# switches_schema.net
KiCad netlist of a schematic drawn in EAGLE
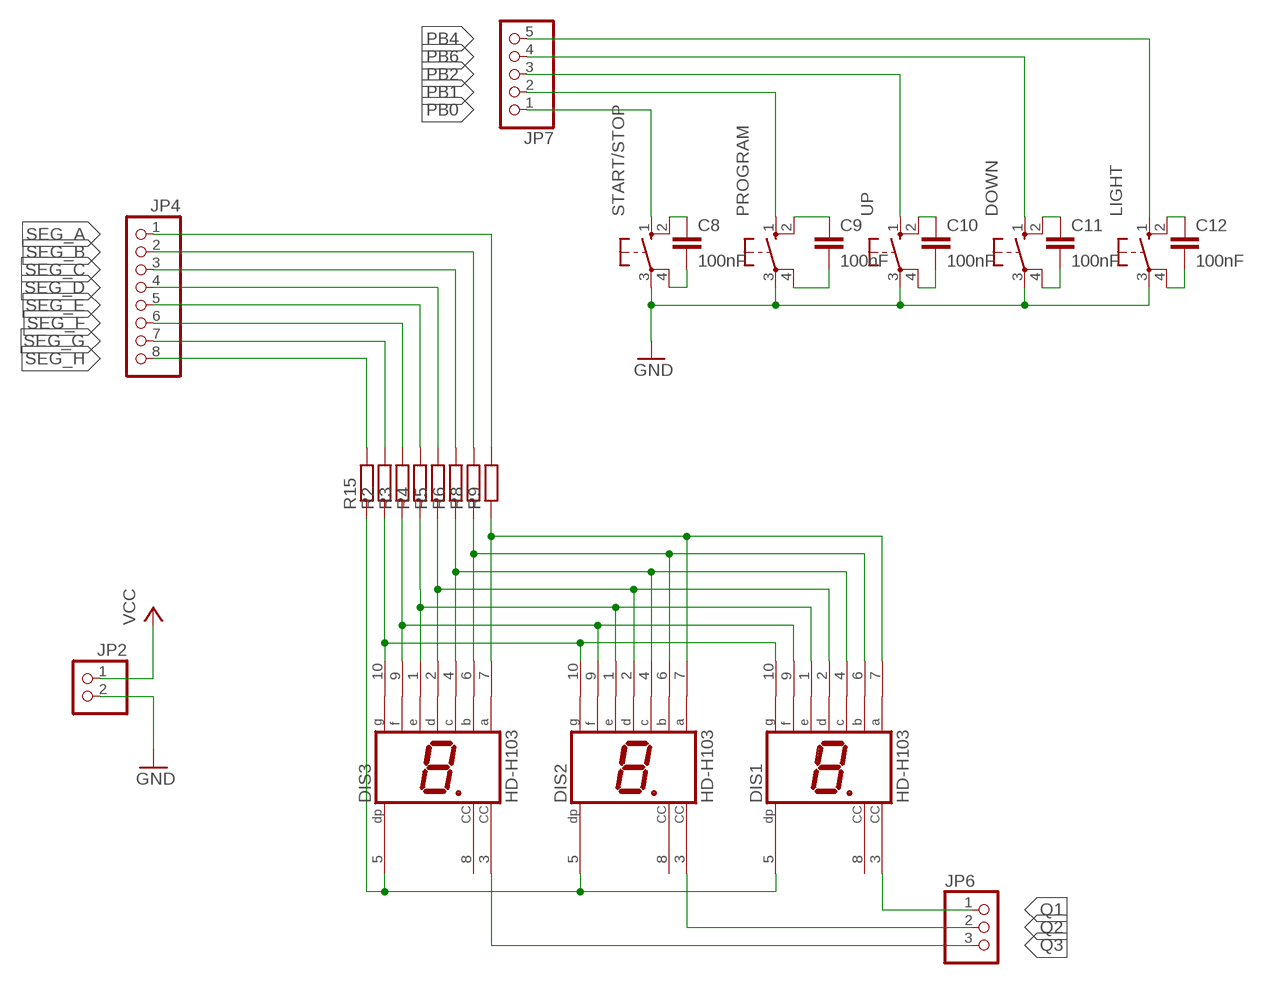
[diagram p0: schematic, sheet 1]

(export (version "E")
  (design (tool "Eeschema 10.0.6"))
  (components
    (comp (ref "C8")
      (value "100nF")
      (footprint "eagle-import:C025-024X044")
      (libsource (lib "eagle-import") (part "C-EU025-024X044"))
    )
    (comp (ref "C9")
      (value "100nF")
      (footprint "eagle-import:C025-024X044")
      (libsource (lib "eagle-import") (part "C-EU025-024X044"))
    )
    (comp (ref "C10")
      (value "100nF")
      (footprint "eagle-import:C025-024X044")
      (libsource (lib "eagle-import") (part "C-EU025-024X044"))
    )
    (comp (ref "C11")
      (value "100nF")
      (footprint "eagle-import:C025-024X044")
      (libsource (lib "eagle-import") (part "C-EU025-024X044"))
    )
    (comp (ref "C12")
      (value "100nF")
      (footprint "eagle-import:C025-024X044")
      (libsource (lib "eagle-import") (part "C-EU025-024X044"))
    )
    (comp (ref "DIS1")
      (value "HD-H103")
      (footprint "eagle-import:HDSP-M")
      (libsource (lib "eagle-import") (part "HD-H103"))
    )
    (comp (ref "DIS2")
      (value "HD-H103")
      (footprint "eagle-import:HDSP-M")
      (libsource (lib "eagle-import") (part "HD-H103"))
    )
    (comp (ref "DIS3")
      (value "HD-H103")
      (footprint "eagle-import:HDSP-M")
      (libsource (lib "eagle-import") (part "HD-H103"))
    )
    (comp (ref "DOWN")
      (value "10-XX")
      (footprint "eagle-import:B3F-10XX")
      (fields (field (name "MPN") "B3F-1000"))
      (libsource (lib "eagle-import") (part "10-XX"))
    )
    (comp (ref "JP2")
      (value "PINHD-1X2")
      (footprint "eagle-import:1X02")
      (libsource (lib "eagle-import") (part "PINHD-1X2"))
    )
    (comp (ref "JP4")
      (value "PINHD-1X8")
      (footprint "eagle-import:1X08")
      (libsource (lib "eagle-import") (part "PINHD-1X8"))
    )
    (comp (ref "JP6")
      (value "PINHD-1X3")
      (footprint "eagle-import:1X03")
      (libsource (lib "eagle-import") (part "PINHD-1X3"))
    )
    (comp (ref "JP7")
      (value "PINHD-1X5")
      (footprint "eagle-import:1X05")
      (libsource (lib "eagle-import") (part "PINHD-1X5"))
    )
    (comp (ref "LIGHT")
      (value "10-XX")
      (footprint "eagle-import:B3F-10XX")
      (fields (field (name "MPN") "B3F-1000"))
      (libsource (lib "eagle-import") (part "10-XX"))
    )
    (comp (ref "PROGRAM")
      (value "10-XX")
      (footprint "eagle-import:B3F-10XX")
      (fields (field (name "MPN") "B3F-1000"))
      (libsource (lib "eagle-import") (part "10-XX"))
    )
    (comp (ref "R2")
      (value "R-EU_0204/7")
      (footprint "eagle-import:0204_7")
      (libsource (lib "eagle-import") (part "R-EU_0204/7"))
    )
    (comp (ref "R3")
      (value "R-EU_0204/7")
      (footprint "eagle-import:0204_7")
      (libsource (lib "eagle-import") (part "R-EU_0204/7"))
    )
    (comp (ref "R4")
      (value "R-EU_0204/7")
      (footprint "eagle-import:0204_7")
      (libsource (lib "eagle-import") (part "R-EU_0204/7"))
    )
    (comp (ref "R5")
      (value "R-EU_0204/7")
      (footprint "eagle-import:0204_7")
      (libsource (lib "eagle-import") (part "R-EU_0204/7"))
    )
    (comp (ref "R6")
      (value "R-EU_0204/7")
      (footprint "eagle-import:0204_7")
      (libsource (lib "eagle-import") (part "R-EU_0204/7"))
    )
    (comp (ref "R8")
      (value "R-EU_0204/7")
      (footprint "eagle-import:0204_7")
      (libsource (lib "eagle-import") (part "R-EU_0204/7"))
    )
    (comp (ref "R9")
      (value "R-EU_0204/7")
      (footprint "eagle-import:0204_7")
      (libsource (lib "eagle-import") (part "R-EU_0204/7"))
    )
    (comp (ref "R15")
      (value "R-EU_0204/7")
      (footprint "eagle-import:0204_7")
      (libsource (lib "eagle-import") (part "R-EU_0204/7"))
    )
    (comp (ref "START/STOP")
      (value "10-XX")
      (footprint "eagle-import:B3F-10XX")
      (fields (field (name "MPN") "B3F-1000"))
      (libsource (lib "eagle-import") (part "10-XX"))
    )
    (comp (ref "UP")
      (value "10-XX")
      (footprint "eagle-import:B3F-10XX")
      (fields (field (name "MPN") "B3F-1000"))
      (libsource (lib "eagle-import") (part "10-XX"))
    )
  )
  (nets
    (net (code "1") (name "GND") (class "Default")
      (node (ref "DOWN") (pin "3") (pinfunction "P_3") (pintype "passive"))
      (node (ref "JP2") (pin "2") (pinfunction "2_2") (pintype "passive"))
      (node (ref "LIGHT") (pin "3") (pinfunction "P_3") (pintype "passive"))
      (node (ref "PROGRAM") (pin "3") (pinfunction "P_3") (pintype "passive"))
      (node (ref "START/STOP") (pin "3") (pinfunction "P_3") (pintype "passive"))
      (node (ref "UP") (pin "3") (pinfunction "P_3") (pintype "passive"))
    )
    (net (code "2") (name "Net-(DIS1-A)") (class "Default")
      (node (ref "DIS1") (pin "7") (pinfunction "A_7") (pintype "passive"))
      (node (ref "DIS2") (pin "7") (pinfunction "A_7") (pintype "passive"))
      (node (ref "DIS3") (pin "7") (pinfunction "A_7") (pintype "passive"))
      (node (ref "R9") (pin "1") (pinfunction "1_1") (pintype "passive"))
    )
    (net (code "3") (name "Net-(DIS1-B)") (class "Default")
      (node (ref "DIS1") (pin "6") (pinfunction "B_6") (pintype "passive"))
      (node (ref "DIS2") (pin "6") (pinfunction "B_6") (pintype "passive"))
      (node (ref "DIS3") (pin "6") (pinfunction "B_6") (pintype "passive"))
      (node (ref "R8") (pin "1") (pinfunction "1_1") (pintype "passive"))
    )
    (net (code "4") (name "Net-(DIS1-C)") (class "Default")
      (node (ref "DIS1") (pin "4") (pinfunction "C_4") (pintype "passive"))
      (node (ref "DIS2") (pin "4") (pinfunction "C_4") (pintype "passive"))
      (node (ref "DIS3") (pin "4") (pinfunction "C_4") (pintype "passive"))
      (node (ref "R6") (pin "1") (pinfunction "1_1") (pintype "passive"))
    )
    (net (code "5") (name "Net-(DIS1-D)") (class "Default")
      (node (ref "DIS1") (pin "2") (pinfunction "D_2") (pintype "passive"))
      (node (ref "DIS2") (pin "2") (pinfunction "D_2") (pintype "passive"))
      (node (ref "DIS3") (pin "2") (pinfunction "D_2") (pintype "passive"))
      (node (ref "R5") (pin "1") (pinfunction "1_1") (pintype "passive"))
    )
    (net (code "6") (name "Net-(DIS1-DP)") (class "Default")
      (node (ref "DIS1") (pin "5") (pinfunction "DP_5") (pintype "passive"))
      (node (ref "DIS2") (pin "5") (pinfunction "DP_5") (pintype "passive"))
      (node (ref "DIS3") (pin "5") (pinfunction "DP_5") (pintype "passive"))
      (node (ref "R15") (pin "1") (pinfunction "1_1") (pintype "passive"))
    )
    (net (code "7") (name "Net-(DIS1-E)") (class "Default")
      (node (ref "DIS1") (pin "1") (pinfunction "E_1") (pintype "passive"))
      (node (ref "DIS2") (pin "1") (pinfunction "E_1") (pintype "passive"))
      (node (ref "DIS3") (pin "1") (pinfunction "E_1") (pintype "passive"))
      (node (ref "R4") (pin "1") (pinfunction "1_1") (pintype "passive"))
    )
    (net (code "8") (name "Net-(DIS1-F)") (class "Default")
      (node (ref "DIS1") (pin "9") (pinfunction "F_9") (pintype "passive"))
      (node (ref "DIS2") (pin "9") (pinfunction "F_9") (pintype "passive"))
      (node (ref "DIS3") (pin "9") (pinfunction "F_9") (pintype "passive"))
      (node (ref "R3") (pin "1") (pinfunction "1_1") (pintype "passive"))
    )
    (net (code "9") (name "Net-(DIS1-G)") (class "Default")
      (node (ref "DIS1") (pin "10") (pinfunction "G_10") (pintype "passive"))
      (node (ref "DIS2") (pin "10") (pinfunction "G_10") (pintype "passive"))
      (node (ref "DIS3") (pin "10") (pinfunction "G_10") (pintype "passive"))
      (node (ref "R2") (pin "1") (pinfunction "1_1") (pintype "passive"))
    )
    (net (code "10") (name "Net-(DOWN-P1)") (class "Default")
      (node (ref "C11") (pin "2") (pinfunction "2_2") (pintype "passive"))
      (node (ref "DOWN") (pin "4") (pinfunction "P1_4") (pintype "passive"))
    )
    (net (code "11") (name "Net-(DOWN-S1)") (class "Default")
      (node (ref "C11") (pin "1") (pinfunction "1_1") (pintype "passive"))
      (node (ref "DOWN") (pin "2") (pinfunction "S1_2") (pintype "passive"))
    )
    (net (code "12") (name "Net-(LIGHT-P1)") (class "Default")
      (node (ref "C12") (pin "2") (pinfunction "2_2") (pintype "passive"))
      (node (ref "LIGHT") (pin "4") (pinfunction "P1_4") (pintype "passive"))
    )
    (net (code "13") (name "Net-(LIGHT-S1)") (class "Default")
      (node (ref "C12") (pin "1") (pinfunction "1_1") (pintype "passive"))
      (node (ref "LIGHT") (pin "2") (pinfunction "S1_2") (pintype "passive"))
    )
    (net (code "14") (name "Net-(PROGRAM-P1)") (class "Default")
      (node (ref "C9") (pin "2") (pinfunction "2_2") (pintype "passive"))
      (node (ref "PROGRAM") (pin "4") (pinfunction "P1_4") (pintype "passive"))
    )
    (net (code "15") (name "Net-(PROGRAM-S1)") (class "Default")
      (node (ref "C9") (pin "1") (pinfunction "1_1") (pintype "passive"))
      (node (ref "PROGRAM") (pin "2") (pinfunction "S1_2") (pintype "passive"))
    )
    (net (code "16") (name "Net-(START/STOP-P1)") (class "Default")
      (node (ref "C8") (pin "2") (pinfunction "2_2") (pintype "passive"))
      (node (ref "START/STOP") (pin "4") (pinfunction "P1_4") (pintype "passive"))
    )
    (net (code "17") (name "Net-(START/STOP-S1)") (class "Default")
      (node (ref "C8") (pin "1") (pinfunction "1_1") (pintype "passive"))
      (node (ref "START/STOP") (pin "2") (pinfunction "S1_2") (pintype "passive"))
    )
    (net (code "18") (name "Net-(UP-P1)") (class "Default")
      (node (ref "C10") (pin "2") (pinfunction "2_2") (pintype "passive"))
      (node (ref "UP") (pin "4") (pinfunction "P1_4") (pintype "passive"))
    )
    (net (code "19") (name "Net-(UP-S1)") (class "Default")
      (node (ref "C10") (pin "1") (pinfunction "1_1") (pintype "passive"))
      (node (ref "UP") (pin "2") (pinfunction "S1_2") (pintype "passive"))
    )
    (net (code "20") (name "PB0") (class "Default")
      (node (ref "JP7") (pin "1") (pinfunction "1_1") (pintype "passive"))
      (node (ref "START/STOP") (pin "1") (pinfunction "S_1") (pintype "passive"))
    )
    (net (code "21") (name "PB1") (class "Default")
      (node (ref "JP7") (pin "2") (pinfunction "2_2") (pintype "passive"))
      (node (ref "PROGRAM") (pin "1") (pinfunction "S_1") (pintype "passive"))
    )
    (net (code "22") (name "PB2") (class "Default")
      (node (ref "JP7") (pin "3") (pinfunction "3_3") (pintype "passive"))
      (node (ref "UP") (pin "1") (pinfunction "S_1") (pintype "passive"))
    )
    (net (code "23") (name "PB4") (class "Default")
      (node (ref "JP7") (pin "5") (pinfunction "5_5") (pintype "passive"))
      (node (ref "LIGHT") (pin "1") (pinfunction "S_1") (pintype "passive"))
    )
    (net (code "24") (name "PB6") (class "Default")
      (node (ref "DOWN") (pin "1") (pinfunction "S_1") (pintype "passive"))
      (node (ref "JP7") (pin "4") (pinfunction "4_4") (pintype "passive"))
    )
    (net (code "25") (name "Q1") (class "Default")
      (node (ref "DIS1") (pin "3") (pinfunction "CC_3") (pintype "passive"))
      (node (ref "JP6") (pin "1") (pinfunction "1_1") (pintype "passive"))
    )
    (net (code "26") (name "Q2") (class "Default")
      (node (ref "DIS2") (pin "3") (pinfunction "CC_3") (pintype "passive"))
      (node (ref "JP6") (pin "2") (pinfunction "2_2") (pintype "passive"))
    )
    (net (code "27") (name "Q3") (class "Default")
      (node (ref "DIS3") (pin "3") (pinfunction "CC_3") (pintype "passive"))
      (node (ref "JP6") (pin "3") (pinfunction "3_3") (pintype "passive"))
    )
    (net (code "28") (name "SEG_A") (class "Default")
      (node (ref "JP4") (pin "1") (pinfunction "1_1") (pintype "passive"))
      (node (ref "R9") (pin "2") (pinfunction "2_2") (pintype "passive"))
    )
    (net (code "29") (name "SEG_B") (class "Default")
      (node (ref "JP4") (pin "2") (pinfunction "2_2") (pintype "passive"))
      (node (ref "R8") (pin "2") (pinfunction "2_2") (pintype "passive"))
    )
    (net (code "30") (name "SEG_C") (class "Default")
      (node (ref "JP4") (pin "3") (pinfunction "3_3") (pintype "passive"))
      (node (ref "R6") (pin "2") (pinfunction "2_2") (pintype "passive"))
    )
    (net (code "31") (name "SEG_D") (class "Default")
      (node (ref "JP4") (pin "4") (pinfunction "4_4") (pintype "passive"))
      (node (ref "R5") (pin "2") (pinfunction "2_2") (pintype "passive"))
    )
    (net (code "32") (name "SEG_E") (class "Default")
      (node (ref "JP4") (pin "5") (pinfunction "5_5") (pintype "passive"))
      (node (ref "R4") (pin "2") (pinfunction "2_2") (pintype "passive"))
    )
    (net (code "33") (name "SEG_F") (class "Default")
      (node (ref "JP4") (pin "6") (pinfunction "6_6") (pintype "passive"))
      (node (ref "R3") (pin "2") (pinfunction "2_2") (pintype "passive"))
    )
    (net (code "34") (name "SEG_G") (class "Default")
      (node (ref "JP4") (pin "7") (pinfunction "7_7") (pintype "passive"))
      (node (ref "R2") (pin "2") (pinfunction "2_2") (pintype "passive"))
    )
    (net (code "35") (name "SEG_H") (class "Default")
      (node (ref "JP4") (pin "8") (pinfunction "8_8") (pintype "passive"))
      (node (ref "R15") (pin "2") (pinfunction "2_2") (pintype "passive"))
    )
    (net (code "36") (name "VCC") (class "Default")
      (node (ref "JP2") (pin "1") (pinfunction "1_1") (pintype "passive"))
    )
    (net (code "37") (name "unconnected-(DIS1-CC-Pad8)") (class "Default")
      (node (ref "DIS1") (pin "8") (pinfunction "CC_8") (pintype "passive"))
    )
    (net (code "38") (name "unconnected-(DIS2-CC-Pad8)") (class "Default")
      (node (ref "DIS2") (pin "8") (pinfunction "CC_8") (pintype "passive"))
    )
    (net (code "39") (name "unconnected-(DIS3-CC-Pad8)") (class "Default")
      (node (ref "DIS3") (pin "8") (pinfunction "CC_8") (pintype "passive"))
    )
  )
)
